# Adafruit_ItsyBitsy_nRF52840_Express.net
KiCad netlist of a schematic drawn in EAGLE
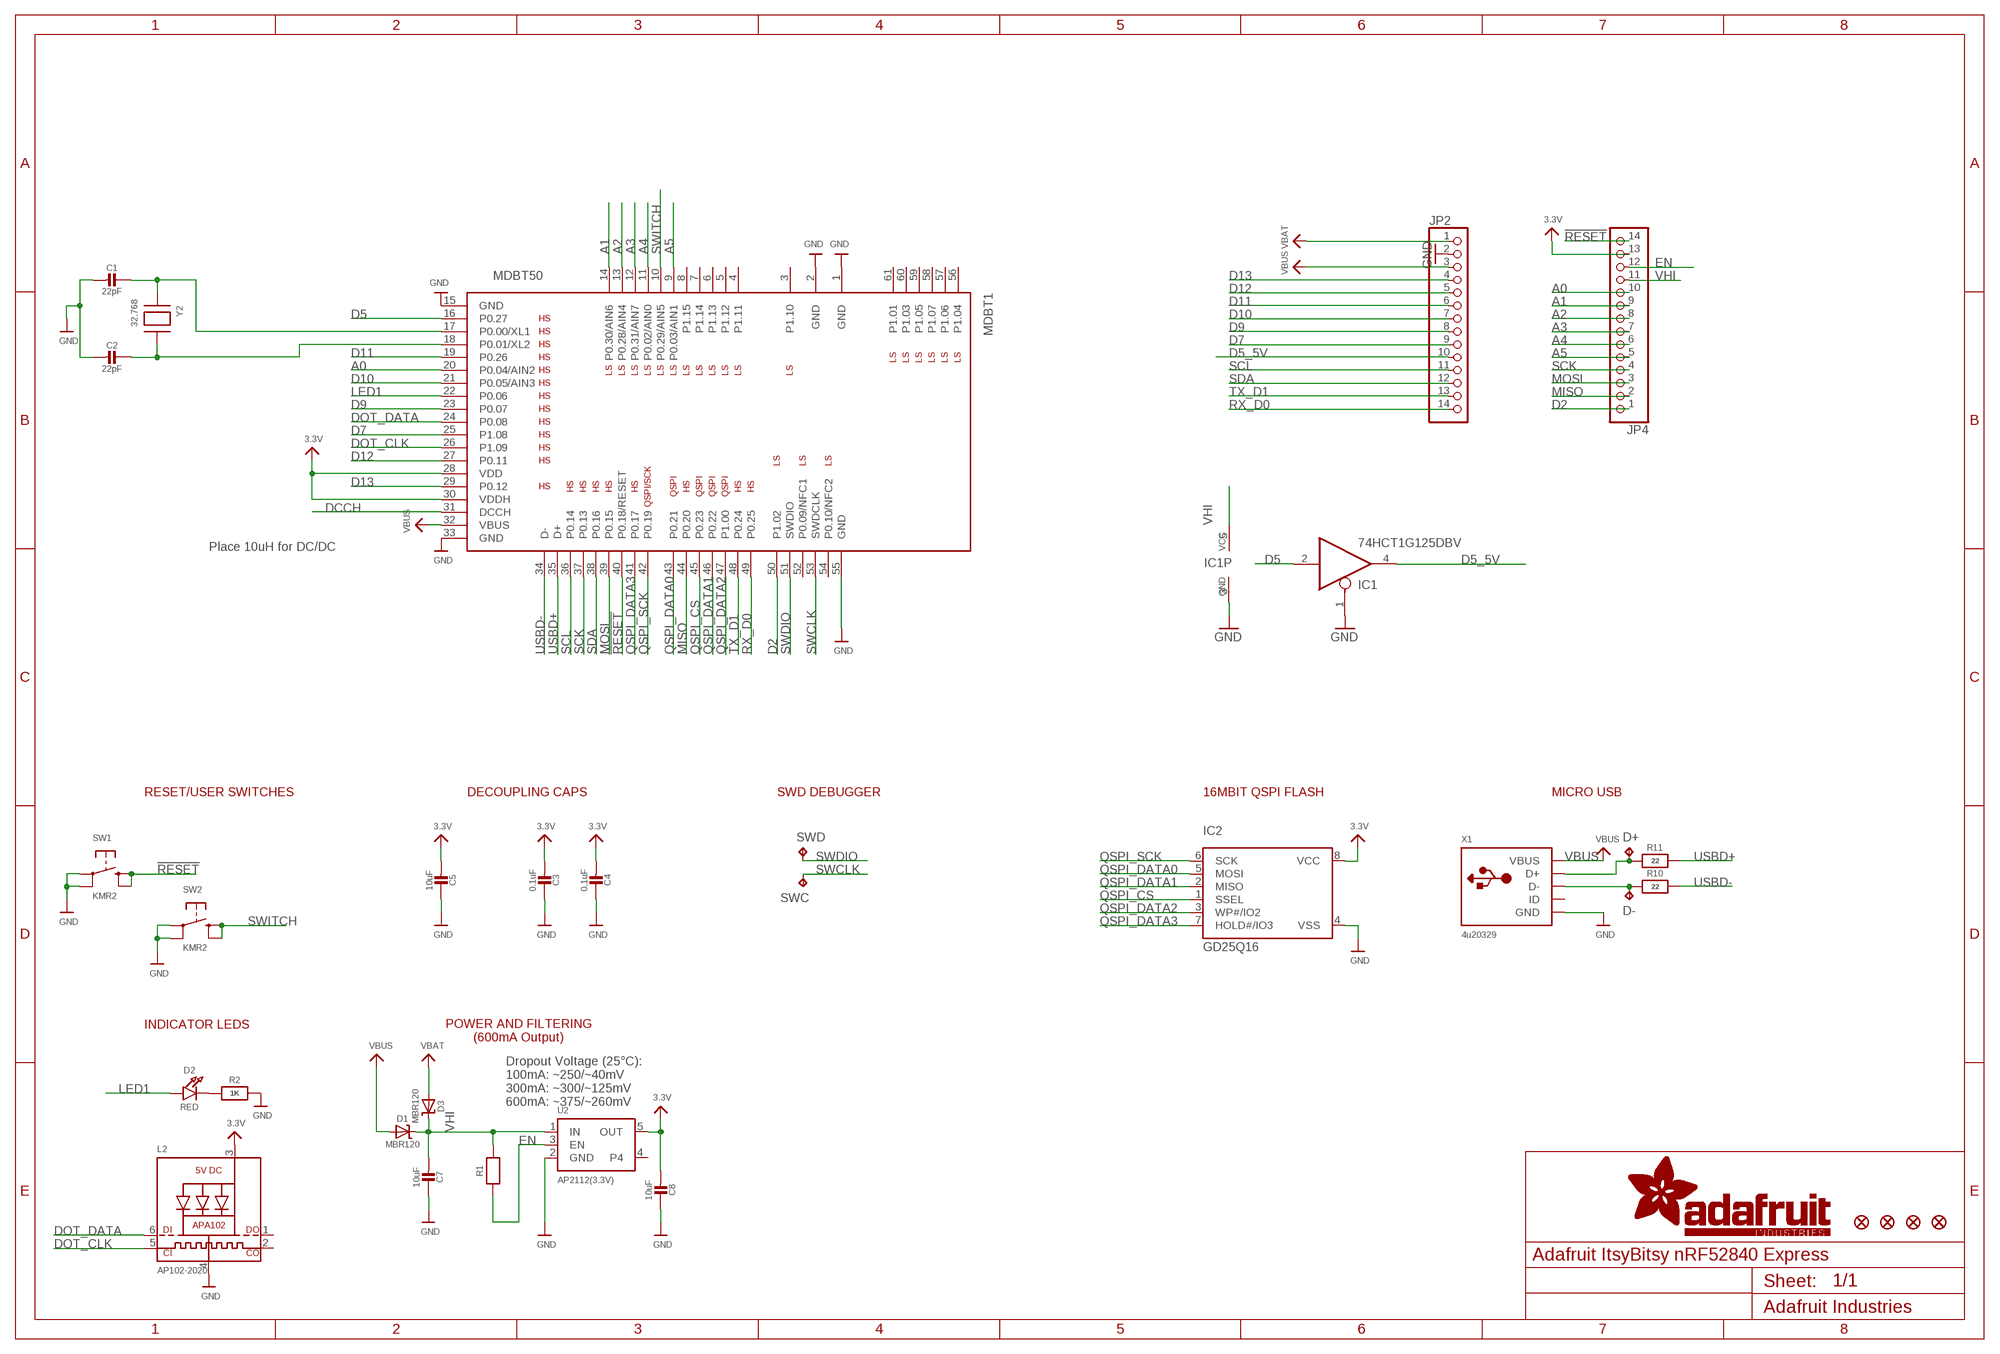
[diagram p0: schematic, sheet 1]

(export (version "E")
  (design (tool "Eeschema 10.0.6"))
  (components
    (comp (ref "C1")
      (value "22pF")
      (footprint "eagle-import:_0603MP")
      (libsource (lib "eagle-import") (part "CAP_CERAMIC_0603MP"))
    )
    (comp (ref "C2")
      (value "22pF")
      (footprint "eagle-import:_0603MP")
      (libsource (lib "eagle-import") (part "CAP_CERAMIC_0603MP"))
    )
    (comp (ref "C3")
      (value "0.1uF")
      (footprint "eagle-import:0603-NO")
      (libsource (lib "eagle-import") (part "CAP_CERAMIC0603_NO"))
    )
    (comp (ref "C4")
      (value "0.1uF")
      (footprint "eagle-import:0603-NO")
      (libsource (lib "eagle-import") (part "CAP_CERAMIC0603_NO"))
    )
    (comp (ref "C5")
      (value "10uF")
      (footprint "eagle-import:0805-NO")
      (libsource (lib "eagle-import") (part "CAP_CERAMIC0805-NOOUTLINE"))
    )
    (comp (ref "C7")
      (value "10uF")
      (footprint "eagle-import:0805-NO")
      (libsource (lib "eagle-import") (part "CAP_CERAMIC0805-NOOUTLINE"))
    )
    (comp (ref "C8")
      (value "10uF")
      (footprint "eagle-import:0805-NO")
      (libsource (lib "eagle-import") (part "CAP_CERAMIC0805-NOOUTLINE"))
    )
    (comp (ref "D+")
      (value "TPTP10R")
      (footprint "eagle-import:TP10R")
      (libsource (lib "eagle-import") (part "TPTP10R"))
    )
    (comp (ref "D-")
      (value "TPTP10R")
      (footprint "eagle-import:TP10R")
      (libsource (lib "eagle-import") (part "TPTP10R"))
    )
    (comp (ref "D1")
      (value "MBR120")
      (footprint "eagle-import:SOD-123")
      (libsource (lib "eagle-import") (part "DIODE-SCHOTTKYSOD-123"))
    )
    (comp (ref "D2")
      (value "RED")
      (footprint "eagle-import:CHIPLED_0805_NOOUTLINE")
      (libsource (lib "eagle-import") (part "LED0805_NOOUTLINE"))
    )
    (comp (ref "D3")
      (value "MBR120")
      (footprint "eagle-import:SOD-123")
      (libsource (lib "eagle-import") (part "DIODE-SCHOTTKYSOD-123"))
    )
    (comp (ref "FID1")
      (value "FIDUCIAL_1MM")
      (footprint "eagle-import:FIDUCIAL_1MM")
      (libsource (lib "eagle-import") (part "FIDUCIAL_1MM"))
    )
    (comp (ref "FID2")
      (value "FIDUCIAL_1MM")
      (footprint "eagle-import:FIDUCIAL_1MM")
      (libsource (lib "eagle-import") (part "FIDUCIAL_1MM"))
    )
    (comp (ref "FID3")
      (value "FIDUCIAL_1MM")
      (footprint "eagle-import:FIDUCIAL_1MM")
      (libsource (lib "eagle-import") (part "FIDUCIAL_1MM"))
    )
    (comp (ref "FID4")
      (value "FIDUCIAL_1MM")
      (footprint "eagle-import:FIDUCIAL_1MM")
      (libsource (lib "eagle-import") (part "FIDUCIAL_1MM"))
    )
    (comp (ref "IC1")
      (value "74HCT1G125DBV")
      (footprint "eagle-import:SOT23-5")
      (libsource (lib "eagle-import") (part "741G125DBVAHC"))
    )
    (comp (ref "IC2")
      (value "GD25Q16")
      (footprint "eagle-import:USON8")
      (libsource (lib "eagle-import") (part "SPIFLASH_8PINUX"))
    )
    (comp (ref "JP2")
      (value "HEADER-1X14")
      (footprint "eagle-import:1X14_ROUND70")
      (libsource (lib "eagle-import") (part "HEADER-1X14"))
    )
    (comp (ref "JP4")
      (value "HEADER-1X14")
      (footprint "eagle-import:1X14_ROUND70")
      (libsource (lib "eagle-import") (part "HEADER-1X14"))
    )
    (comp (ref "L2")
      (value "AP102-2020")
      (footprint "eagle-import:APA102_2020")
      (libsource (lib "eagle-import") (part "APA1022020"))
    )
    (comp (ref "MDBT1")
      (value "MDBT50")
      (footprint "eagle-import:MDBT50")
      (libsource (lib "eagle-import") (part "MDBT50"))
    )
    (comp (ref "R1")
      (value "10K")
      (footprint "eagle-import:0603-NO")
      (libsource (lib "eagle-import") (part "RESISTOR_0603_NOOUT"))
    )
    (comp (ref "R2")
      (value "1K")
      (footprint "eagle-import:0603-NO")
      (libsource (lib "eagle-import") (part "RESISTOR_0603_NOOUT"))
    )
    (comp (ref "R10")
      (value "22")
      (footprint "eagle-import:0603-NO")
      (libsource (lib "eagle-import") (part "RESISTOR_0603_NOOUT"))
    )
    (comp (ref "R11")
      (value "22")
      (footprint "eagle-import:0603-NO")
      (libsource (lib "eagle-import") (part "RESISTOR_0603_NOOUT"))
    )
    (comp (ref "SW1")
      (value "KMR2")
      (footprint "eagle-import:BTN_KMR2_4.6X2.8")
      (libsource (lib "eagle-import") (part "SWITCH_TACT_SMT4.6X2.8"))
    )
    (comp (ref "SW2")
      (value "KMR2")
      (footprint "eagle-import:BTN_KMR2_4.6X2.8")
      (libsource (lib "eagle-import") (part "SWITCH_TACT_SMT4.6X2.8"))
    )
    (comp (ref "SWC")
      (value "TPTP13R")
      (footprint "eagle-import:TP13R")
      (libsource (lib "eagle-import") (part "TPTP13R"))
    )
    (comp (ref "SWD")
      (value "TPTP13R")
      (footprint "eagle-import:TP13R")
      (libsource (lib "eagle-import") (part "TPTP13R"))
    )
    (comp (ref "U2")
      (value "AP2112(3.3V)")
      (footprint "eagle-import:SOT23-5")
      (libsource (lib "eagle-import") (part "VREG_SOT23-5"))
    )
    (comp (ref "X1")
      (value "4u20329")
      (footprint "eagle-import:4UCONN_20329_V2")
      (libsource (lib "eagle-import") (part "USB_MICRO_20329_V2"))
    )
    (comp (ref "Y2")
      (value "32.768")
      (footprint "eagle-import:XTAL3215")
      (libsource (lib "eagle-import") (part "XTAL-3.2X1.5"))
    )
  )
  (nets
    (net (code "1") (name "/A0") (class "Default")
      (node (ref "JP4") (pin "10") (pinfunction "10_10") (pintype "passive"))
      (node (ref "MDBT1") (pin "20") (pinfunction "P0.04/AIN2_20") (pintype "bidirectional"))
    )
    (net (code "2") (name "/A1") (class "Default")
      (node (ref "JP4") (pin "9") (pinfunction "9_9") (pintype "passive"))
      (node (ref "MDBT1") (pin "14") (pinfunction "P0.30/AIN6_14") (pintype "bidirectional"))
    )
    (net (code "3") (name "/A2") (class "Default")
      (node (ref "JP4") (pin "8") (pinfunction "8_8") (pintype "passive"))
      (node (ref "MDBT1") (pin "13") (pinfunction "P0.28/AIN4_13") (pintype "bidirectional"))
    )
    (net (code "4") (name "/A3") (class "Default")
      (node (ref "JP4") (pin "7") (pinfunction "7_7") (pintype "passive"))
      (node (ref "MDBT1") (pin "12") (pinfunction "P0.31/AIN7_12") (pintype "bidirectional"))
    )
    (net (code "5") (name "/A4") (class "Default")
      (node (ref "JP4") (pin "6") (pinfunction "6_6") (pintype "passive"))
      (node (ref "MDBT1") (pin "11") (pinfunction "P0.02/AIN0_11") (pintype "bidirectional"))
    )
    (net (code "6") (name "/A5") (class "Default")
      (node (ref "JP4") (pin "5") (pinfunction "5_5") (pintype "passive"))
      (node (ref "MDBT1") (pin "9") (pinfunction "P0.03/AIN1_9") (pintype "bidirectional"))
    )
    (net (code "7") (name "/D2") (class "Default")
      (node (ref "JP4") (pin "1") (pinfunction "1_1") (pintype "passive"))
      (node (ref "MDBT1") (pin "50") (pinfunction "P1.02_50") (pintype "bidirectional"))
    )
    (net (code "8") (name "/D5") (class "Default")
      (node (ref "IC1") (pin "2") (pinfunction "I_2") (pintype "input"))
      (node (ref "MDBT1") (pin "16") (pinfunction "P0.27_16") (pintype "bidirectional"))
    )
    (net (code "9") (name "/D5_5V") (class "Default")
      (node (ref "IC1") (pin "4") (pinfunction "O_4") (pintype "tri_state"))
      (node (ref "JP2") (pin "10") (pinfunction "10_10") (pintype "passive"))
    )
    (net (code "10") (name "/D7") (class "Default")
      (node (ref "JP2") (pin "9") (pinfunction "9_9") (pintype "passive"))
      (node (ref "MDBT1") (pin "25") (pinfunction "P1.08_25") (pintype "bidirectional"))
    )
    (net (code "11") (name "/D9") (class "Default")
      (node (ref "JP2") (pin "8") (pinfunction "8_8") (pintype "passive"))
      (node (ref "MDBT1") (pin "23") (pinfunction "P0.07_23") (pintype "bidirectional"))
    )
    (net (code "12") (name "/D10") (class "Default")
      (node (ref "JP2") (pin "7") (pinfunction "7_7") (pintype "passive"))
      (node (ref "MDBT1") (pin "21") (pinfunction "P0.05/AIN3_21") (pintype "bidirectional"))
    )
    (net (code "13") (name "/D11") (class "Default")
      (node (ref "JP2") (pin "6") (pinfunction "6_6") (pintype "passive"))
      (node (ref "MDBT1") (pin "19") (pinfunction "P0.26_19") (pintype "bidirectional"))
    )
    (net (code "14") (name "/D12") (class "Default")
      (node (ref "JP2") (pin "5") (pinfunction "5_5") (pintype "passive"))
      (node (ref "MDBT1") (pin "27") (pinfunction "P0.11_27") (pintype "bidirectional"))
    )
    (net (code "15") (name "/D13") (class "Default")
      (node (ref "JP2") (pin "4") (pinfunction "4_4") (pintype "passive"))
      (node (ref "MDBT1") (pin "29") (pinfunction "P0.12_29") (pintype "bidirectional"))
    )
    (net (code "16") (name "/DCCH") (class "Default")
      (node (ref "MDBT1") (pin "31") (pinfunction "DCCH_31") (pintype "bidirectional"))
    )
    (net (code "17") (name "/DOT_CLK") (class "Default")
      (node (ref "L2") (pin "5") (pinfunction "CKI_5") (pintype "input"))
      (node (ref "MDBT1") (pin "26") (pinfunction "P1.09_26") (pintype "bidirectional"))
    )
    (net (code "18") (name "/DOT_DATA") (class "Default")
      (node (ref "L2") (pin "6") (pinfunction "DI_6") (pintype "input"))
      (node (ref "MDBT1") (pin "24") (pinfunction "P0.08_24") (pintype "bidirectional"))
    )
    (net (code "19") (name "/EN") (class "Default")
      (node (ref "JP4") (pin "12") (pinfunction "12_12") (pintype "passive"))
      (node (ref "R1") (pin "1") (pinfunction "1_1") (pintype "passive"))
      (node (ref "U2") (pin "3") (pinfunction "EN_3") (pintype "input"))
    )
    (net (code "20") (name "/LED1") (class "Default")
      (node (ref "D2") (pin "A") (pinfunction "A_A") (pintype "passive"))
      (node (ref "MDBT1") (pin "22") (pinfunction "P0.06_22") (pintype "bidirectional"))
    )
    (net (code "21") (name "/MISO") (class "Default")
      (node (ref "JP4") (pin "2") (pinfunction "2_2") (pintype "passive"))
      (node (ref "MDBT1") (pin "44") (pinfunction "P0.20_44") (pintype "bidirectional"))
    )
    (net (code "22") (name "/MOSI") (class "Default")
      (node (ref "JP4") (pin "3") (pinfunction "3_3") (pintype "passive"))
      (node (ref "MDBT1") (pin "39") (pinfunction "P0.15_39") (pintype "bidirectional"))
    )
    (net (code "23") (name "/QSPI_CS") (class "Default")
      (node (ref "IC2") (pin "1") (pinfunction "SSEL_1") (pintype "bidirectional"))
      (node (ref "MDBT1") (pin "45") (pinfunction "P0.23_45") (pintype "bidirectional"))
    )
    (net (code "24") (name "/QSPI_DATA0") (class "Default")
      (node (ref "IC2") (pin "5") (pinfunction "MOSI_5") (pintype "bidirectional"))
      (node (ref "MDBT1") (pin "43") (pinfunction "P0.21_43") (pintype "bidirectional"))
    )
    (net (code "25") (name "/QSPI_DATA1") (class "Default")
      (node (ref "IC2") (pin "2") (pinfunction "MISO_2") (pintype "bidirectional"))
      (node (ref "MDBT1") (pin "46") (pinfunction "P0.22_46") (pintype "bidirectional"))
    )
    (net (code "26") (name "/QSPI_DATA2") (class "Default")
      (node (ref "IC2") (pin "3") (pinfunction "WP#/IO2_3") (pintype "bidirectional"))
      (node (ref "MDBT1") (pin "47") (pinfunction "P1.00_47") (pintype "bidirectional"))
    )
    (net (code "27") (name "/QSPI_DATA3") (class "Default")
      (node (ref "IC2") (pin "7") (pinfunction "HOLD#/IO3_7") (pintype "bidirectional"))
      (node (ref "MDBT1") (pin "41") (pinfunction "P0.17_41") (pintype "bidirectional"))
    )
    (net (code "28") (name "/QSPI_SCK") (class "Default")
      (node (ref "IC2") (pin "6") (pinfunction "SCK_6") (pintype "bidirectional"))
      (node (ref "MDBT1") (pin "42") (pinfunction "P0.19_42") (pintype "bidirectional"))
    )
    (net (code "29") (name "/RX_D0") (class "Default")
      (node (ref "JP2") (pin "14") (pinfunction "14_14") (pintype "passive"))
      (node (ref "MDBT1") (pin "49") (pinfunction "P0.25_49") (pintype "bidirectional"))
    )
    (net (code "30") (name "/SCK") (class "Default")
      (node (ref "JP4") (pin "4") (pinfunction "4_4") (pintype "passive"))
      (node (ref "MDBT1") (pin "37") (pinfunction "P0.13_37") (pintype "bidirectional"))
    )
    (net (code "31") (name "/SCL") (class "Default")
      (node (ref "JP2") (pin "11") (pinfunction "11_11") (pintype "passive"))
      (node (ref "MDBT1") (pin "36") (pinfunction "P0.14_36") (pintype "bidirectional"))
    )
    (net (code "32") (name "/SDA") (class "Default")
      (node (ref "JP2") (pin "12") (pinfunction "12_12") (pintype "passive"))
      (node (ref "MDBT1") (pin "38") (pinfunction "P0.16_38") (pintype "bidirectional"))
    )
    (net (code "33") (name "/SWCLK") (class "Default")
      (node (ref "MDBT1") (pin "53") (pinfunction "SWDCLK_53") (pintype "bidirectional"))
      (node (ref "SWC") (pin "TP") (pinfunction "TP_TP") (pintype "input"))
    )
    (net (code "34") (name "/SWDIO") (class "Default")
      (node (ref "MDBT1") (pin "51") (pinfunction "SWDIO_51") (pintype "bidirectional"))
      (node (ref "SWD") (pin "TP") (pinfunction "TP_TP") (pintype "input"))
    )
    (net (code "35") (name "/SWITCH") (class "Default")
      (node (ref "MDBT1") (pin "10") (pinfunction "P0.29/AIN5_10") (pintype "bidirectional"))
      (node (ref "SW2") (pin "B") (pinfunction "S_B") (pintype "passive"))
      (node (ref "SW2") (pin "B'") (pinfunction "S1_B'") (pintype "passive"))
    )
    (net (code "36") (name "/TX_D1") (class "Default")
      (node (ref "JP2") (pin "13") (pinfunction "13_13") (pintype "passive"))
      (node (ref "MDBT1") (pin "48") (pinfunction "P0.24_48") (pintype "bidirectional"))
    )
    (net (code "37") (name "/USBD+") (class "Default")
      (node (ref "MDBT1") (pin "35") (pinfunction "D+_35") (pintype "bidirectional"))
      (node (ref "R11") (pin "2") (pinfunction "2_2") (pintype "passive"))
    )
    (net (code "38") (name "/USBD-") (class "Default")
      (node (ref "MDBT1") (pin "34") (pinfunction "D-_34") (pintype "bidirectional"))
      (node (ref "R10") (pin "2") (pinfunction "2_2") (pintype "passive"))
    )
    (net (code "39") (name "/VHI") (class "Default")
      (node (ref "C7") (pin "2") (pinfunction "2_2") (pintype "passive"))
      (node (ref "D1") (pin "C") (pinfunction "C_C") (pintype "passive"))
      (node (ref "D3") (pin "C") (pinfunction "C_C") (pintype "passive"))
      (node (ref "IC1") (pin "5") (pinfunction "VCC_5") (pintype "power_in"))
      (node (ref "JP4") (pin "11") (pinfunction "11_11") (pintype "passive"))
      (node (ref "R1") (pin "2") (pinfunction "2_2") (pintype "passive"))
      (node (ref "U2") (pin "1") (pinfunction "IN_1") (pintype "power_in"))
    )
    (net (code "40") (name "/~{RESET}") (class "Default")
      (node (ref "JP4") (pin "14") (pinfunction "14_14") (pintype "passive"))
      (node (ref "MDBT1") (pin "40") (pinfunction "P0.18/RESET_40") (pintype "bidirectional"))
      (node (ref "SW1") (pin "B") (pinfunction "S_B") (pintype "passive"))
      (node (ref "SW1") (pin "B'") (pinfunction "S1_B'") (pintype "passive"))
    )
    (net (code "41") (name "3.3V") (class "Default")
      (node (ref "C3") (pin "2") (pinfunction "2_2") (pintype "passive"))
      (node (ref "C4") (pin "2") (pinfunction "2_2") (pintype "passive"))
      (node (ref "C5") (pin "2") (pinfunction "2_2") (pintype "passive"))
      (node (ref "C8") (pin "2") (pinfunction "2_2") (pintype "passive"))
      (node (ref "IC2") (pin "8") (pinfunction "VCC_8") (pintype "bidirectional"))
      (node (ref "JP4") (pin "13") (pinfunction "13_13") (pintype "passive"))
      (node (ref "L2") (pin "3") (pinfunction "VDD_3") (pintype "power_in"))
      (node (ref "MDBT1") (pin "28") (pinfunction "VDD_28") (pintype "bidirectional"))
      (node (ref "MDBT1") (pin "30") (pinfunction "VDDH_30") (pintype "bidirectional"))
      (node (ref "U2") (pin "5") (pinfunction "OUT_5") (pintype "power_in"))
    )
    (net (code "42") (name "GND") (class "Default")
      (node (ref "C1") (pin "2") (pinfunction "2_2") (pintype "passive"))
      (node (ref "C2") (pin "2") (pinfunction "2_2") (pintype "passive"))
      (node (ref "C3") (pin "1") (pinfunction "1_1") (pintype "passive"))
      (node (ref "C4") (pin "1") (pinfunction "1_1") (pintype "passive"))
      (node (ref "C5") (pin "1") (pinfunction "1_1") (pintype "passive"))
      (node (ref "C7") (pin "1") (pinfunction "1_1") (pintype "passive"))
      (node (ref "C8") (pin "1") (pinfunction "1_1") (pintype "passive"))
      (node (ref "IC1") (pin "1") (pinfunction "OE_1") (pintype "input"))
      (node (ref "IC1") (pin "3") (pinfunction "GND_3") (pintype "power_in"))
      (node (ref "IC2") (pin "4") (pinfunction "VSS_4") (pintype "bidirectional"))
      (node (ref "JP2") (pin "2") (pinfunction "2_2") (pintype "passive"))
      (node (ref "L2") (pin "4") (pinfunction "GND_4") (pintype "power_in"))
      (node (ref "MDBT1") (pin "1") (pinfunction "GND_1") (pintype "bidirectional"))
      (node (ref "MDBT1") (pin "15") (pinfunction "GND_15") (pintype "bidirectional"))
      (node (ref "MDBT1") (pin "2") (pinfunction "GND_2") (pintype "bidirectional"))
      (node (ref "MDBT1") (pin "33") (pinfunction "GND_33") (pintype "bidirectional"))
      (node (ref "MDBT1") (pin "55") (pinfunction "GND_55") (pintype "bidirectional"))
      (node (ref "R2") (pin "2") (pinfunction "2_2") (pintype "passive"))
      (node (ref "SW1") (pin "A") (pinfunction "P_A") (pintype "passive"))
      (node (ref "SW1") (pin "A'") (pinfunction "P1_A'") (pintype "passive"))
      (node (ref "SW2") (pin "A") (pinfunction "P_A") (pintype "passive"))
      (node (ref "SW2") (pin "A'") (pinfunction "P1_A'") (pintype "passive"))
      (node (ref "U2") (pin "2") (pinfunction "GND_2") (pintype "power_in"))
      (node (ref "X1") (pin "BASE@1") (pinfunction "GND_BASE@1") (pintype "power_in"))
      (node (ref "X1") (pin "BASE@2") (pinfunction "GND_BASE@2") (pintype "power_in"))
      (node (ref "X1") (pin "GND") (pinfunction "GND_GND") (pintype "power_in"))
      (node (ref "X1") (pin "SPRT@1") (pinfunction "GND_SPRT@1") (pintype "power_in"))
      (node (ref "X1") (pin "SPRT@2") (pinfunction "GND_SPRT@2") (pintype "power_in"))
      (node (ref "X1") (pin "SPRT@3") (pinfunction "GND_SPRT@3") (pintype "power_in"))
      (node (ref "X1") (pin "SPRT@4") (pinfunction "GND_SPRT@4") (pintype "power_in"))
    )
    (net (code "43") (name "Net-(D+-PadTP)") (class "Default")
      (node (ref "D+") (pin "TP") (pinfunction "TP_TP") (pintype "input"))
      (node (ref "R11") (pin "1") (pinfunction "1_1") (pintype "passive"))
      (node (ref "X1") (pin "D+") (pinfunction "D+_D+") (pintype "bidirectional"))
    )
    (net (code "44") (name "Net-(D--PadTP)") (class "Default")
      (node (ref "D-") (pin "TP") (pinfunction "TP_TP") (pintype "input"))
      (node (ref "R10") (pin "1") (pinfunction "1_1") (pintype "passive"))
      (node (ref "X1") (pin "D-") (pinfunction "D-_D-") (pintype "bidirectional"))
    )
    (net (code "45") (name "Net-(D2-PadC)") (class "Default")
      (node (ref "D2") (pin "C") (pinfunction "C_C") (pintype "passive"))
      (node (ref "R2") (pin "1") (pinfunction "1_1") (pintype "passive"))
    )
    (net (code "46") (name "Net-(MDBT1-P0.00{slash}XL1)") (class "Default")
      (node (ref "C1") (pin "1") (pinfunction "1_1") (pintype "passive"))
      (node (ref "MDBT1") (pin "17") (pinfunction "P0.00/XL1_17") (pintype "bidirectional"))
      (node (ref "Y2") (pin "P$1") (pinfunction "P$1_P$1") (pintype "bidirectional"))
    )
    (net (code "47") (name "Net-(MDBT1-P0.01{slash}XL2)") (class "Default")
      (node (ref "C2") (pin "1") (pinfunction "1_1") (pintype "passive"))
      (node (ref "MDBT1") (pin "18") (pinfunction "P0.01/XL2_18") (pintype "bidirectional"))
      (node (ref "Y2") (pin "P$2") (pinfunction "P$2_P$2") (pintype "bidirectional"))
    )
    (net (code "48") (name "VBAT") (class "Default")
      (node (ref "D3") (pin "A") (pinfunction "A_A") (pintype "passive"))
      (node (ref "JP2") (pin "1") (pinfunction "1_1") (pintype "passive"))
    )
    (net (code "49") (name "VBUS") (class "Default")
      (node (ref "D1") (pin "A") (pinfunction "A_A") (pintype "passive"))
      (node (ref "JP2") (pin "3") (pinfunction "3_3") (pintype "passive"))
      (node (ref "MDBT1") (pin "32") (pinfunction "VBUS_32") (pintype "bidirectional"))
      (node (ref "X1") (pin "VBUS") (pinfunction "VBUS_VBUS") (pintype "power_in"))
    )
    (net (code "50") (name "unconnected-(L2-CKO-Pad2)") (class "Default")
      (node (ref "L2") (pin "2") (pinfunction "CKO_2") (pintype "output"))
    )
    (net (code "51") (name "unconnected-(L2-DO-Pad1)") (class "Default")
      (node (ref "L2") (pin "1") (pinfunction "DO_1") (pintype "output"))
    )
    (net (code "52") (name "unconnected-(MDBT1-P0.09{slash}NFC1-Pad52)") (class "Default")
      (node (ref "MDBT1") (pin "52") (pinfunction "P0.09/NFC1_52") (pintype "bidirectional"))
    )
    (net (code "53") (name "unconnected-(MDBT1-P0.10{slash}NFC2-Pad54)") (class "Default")
      (node (ref "MDBT1") (pin "54") (pinfunction "P0.10/NFC2_54") (pintype "bidirectional"))
    )
    (net (code "54") (name "unconnected-(MDBT1-P1.01-Pad61)") (class "Default")
      (node (ref "MDBT1") (pin "61") (pinfunction "P1.01_61") (pintype "bidirectional"))
    )
    (net (code "55") (name "unconnected-(MDBT1-P1.03-Pad60)") (class "Default")
      (node (ref "MDBT1") (pin "60") (pinfunction "P1.03_60") (pintype "bidirectional"))
    )
    (net (code "56") (name "unconnected-(MDBT1-P1.04-Pad56)") (class "Default")
      (node (ref "MDBT1") (pin "56") (pinfunction "P1.04_56") (pintype "bidirectional"))
    )
    (net (code "57") (name "unconnected-(MDBT1-P1.05-Pad59)") (class "Default")
      (node (ref "MDBT1") (pin "59") (pinfunction "P1.05_59") (pintype "bidirectional"))
    )
    (net (code "58") (name "unconnected-(MDBT1-P1.06-Pad57)") (class "Default")
      (node (ref "MDBT1") (pin "57") (pinfunction "P1.06_57") (pintype "bidirectional"))
    )
    (net (code "59") (name "unconnected-(MDBT1-P1.07-Pad58)") (class "Default")
      (node (ref "MDBT1") (pin "58") (pinfunction "P1.07_58") (pintype "bidirectional"))
    )
    (net (code "60") (name "unconnected-(MDBT1-P1.10-Pad3)") (class "Default")
      (node (ref "MDBT1") (pin "3") (pinfunction "P1.10_3") (pintype "bidirectional"))
    )
    (net (code "61") (name "unconnected-(MDBT1-P1.11-Pad4)") (class "Default")
      (node (ref "MDBT1") (pin "4") (pinfunction "P1.11_4") (pintype "bidirectional"))
    )
    (net (code "62") (name "unconnected-(MDBT1-P1.12-Pad5)") (class "Default")
      (node (ref "MDBT1") (pin "5") (pinfunction "P1.12_5") (pintype "bidirectional"))
    )
    (net (code "63") (name "unconnected-(MDBT1-P1.13-Pad6)") (class "Default")
      (node (ref "MDBT1") (pin "6") (pinfunction "P1.13_6") (pintype "bidirectional"))
    )
    (net (code "64") (name "unconnected-(MDBT1-P1.14-Pad7)") (class "Default")
      (node (ref "MDBT1") (pin "7") (pinfunction "P1.14_7") (pintype "bidirectional"))
    )
    (net (code "65") (name "unconnected-(MDBT1-P1.15-Pad8)") (class "Default")
      (node (ref "MDBT1") (pin "8") (pinfunction "P1.15_8") (pintype "bidirectional"))
    )
    (net (code "66") (name "unconnected-(U2-P4-Pad4)") (class "Default")
      (node (ref "U2") (pin "4") (pinfunction "P4_4") (pintype "bidirectional"))
    )
    (net (code "67") (name "unconnected-(X1-PadID)") (class "Default")
      (node (ref "X1") (pin "ID") (pinfunction "ID_ID") (pintype "bidirectional"))
    )
  )
)
